# programmer-shield.net
KiCad netlist of a schematic drawn in EAGLE
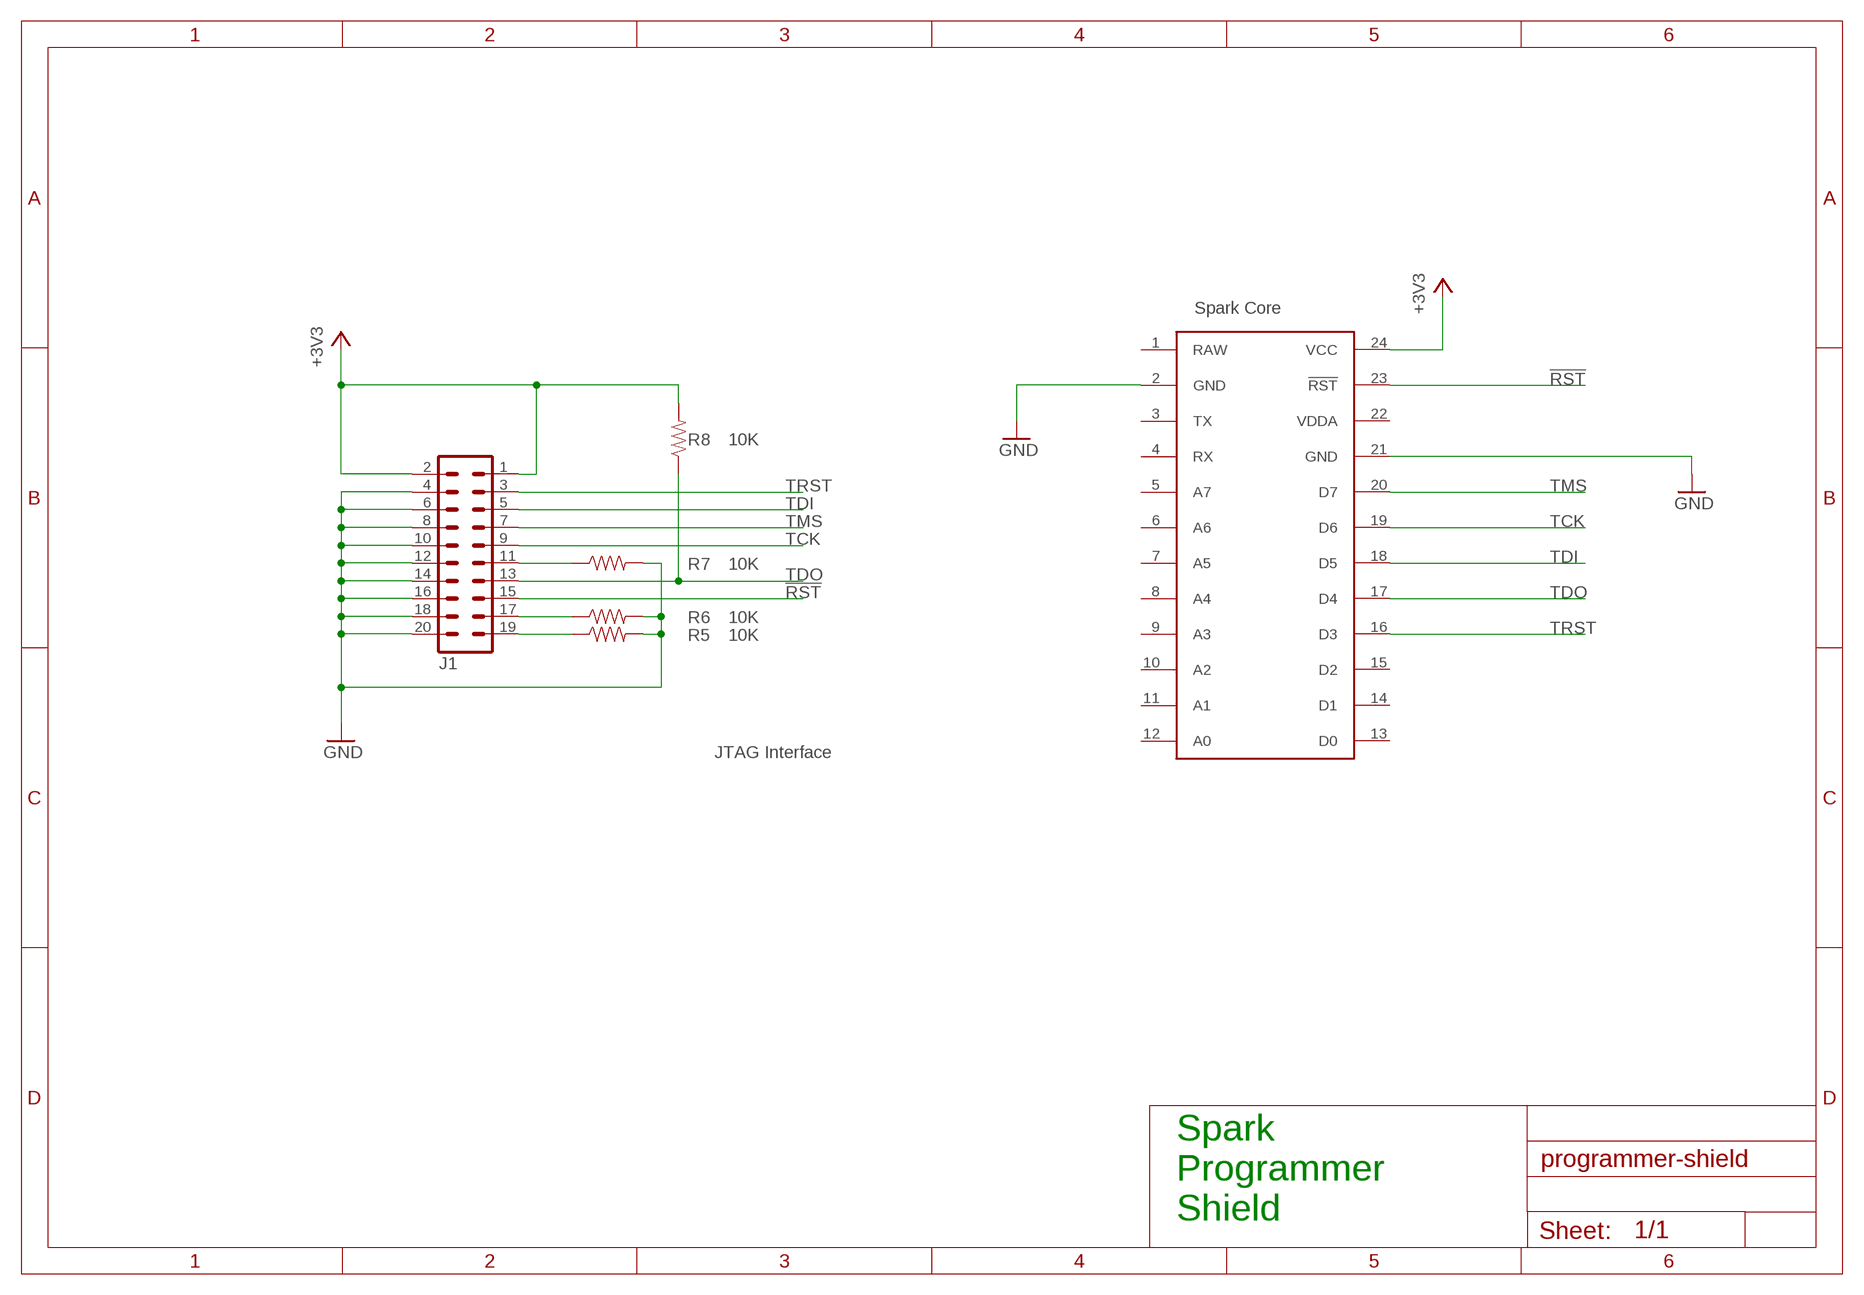
[diagram p0: schematic, sheet 1]

(export (version "E")
  (design (tool "Eeschema 10.0.6"))
  (components
    (comp (ref "J1")
      (value "ML20")
      (footprint "eagle-import:ML20")
      (libsource (lib "eagle-import") (part "ML20"))
    )
    (comp (ref "R5")
      (value "10K")
      (footprint "eagle-import:AXIAL-0.3")
      (libsource (lib "eagle-import") (part "RESISTORAXIAL-0.3"))
    )
    (comp (ref "R6")
      (value "10K")
      (footprint "eagle-import:AXIAL-0.3")
      (libsource (lib "eagle-import") (part "RESISTORAXIAL-0.3"))
    )
    (comp (ref "R7")
      (value "10K")
      (footprint "eagle-import:AXIAL-0.3")
      (libsource (lib "eagle-import") (part "RESISTORAXIAL-0.3"))
    )
    (comp (ref "R8")
      (value "10K")
      (footprint "eagle-import:AXIAL-0.3")
      (libsource (lib "eagle-import") (part "RESISTORAXIAL-0.3"))
    )
    (comp (ref "U$1")
      (value "SPARK_CORECORE")
      (footprint "eagle-import:SPARK_CORE")
      (libsource (lib "eagle-import") (part "SPARK_CORECORE"))
    )
  )
  (nets
    (net (code "1") (name "+3V3") (class "Default")
      (node (ref "J1") (pin "1") (pinfunction "1_1") (pintype "passive"))
      (node (ref "J1") (pin "2") (pinfunction "2_2") (pintype "passive"))
      (node (ref "R8") (pin "P$2") (pinfunction "2_P$2") (pintype "passive"))
      (node (ref "U$1") (pin "24") (pinfunction "VCC_24") (pintype "power_in"))
    )
    (net (code "2") (name "/RAW") (class "Default")
      (node (ref "U$1") (pin "1") (pinfunction "RAW_1") (pintype "power_in"))
    )
    (net (code "3") (name "/TCK") (class "Default")
      (node (ref "J1") (pin "9") (pinfunction "9_9") (pintype "passive"))
      (node (ref "U$1") (pin "19") (pinfunction "D6_19") (pintype "bidirectional"))
    )
    (net (code "4") (name "/TDI") (class "Default")
      (node (ref "J1") (pin "5") (pinfunction "5_5") (pintype "passive"))
      (node (ref "U$1") (pin "18") (pinfunction "D5_18") (pintype "bidirectional"))
    )
    (net (code "5") (name "/TDO") (class "Default")
      (node (ref "J1") (pin "13") (pinfunction "13_13") (pintype "passive"))
      (node (ref "R8") (pin "P$1") (pinfunction "1_P$1") (pintype "passive"))
      (node (ref "U$1") (pin "17") (pinfunction "D4_17") (pintype "bidirectional"))
    )
    (net (code "6") (name "/TMS") (class "Default")
      (node (ref "J1") (pin "7") (pinfunction "7_7") (pintype "passive"))
      (node (ref "U$1") (pin "20") (pinfunction "D7_20") (pintype "bidirectional"))
    )
    (net (code "7") (name "/TRST") (class "Default")
      (node (ref "J1") (pin "3") (pinfunction "3_3") (pintype "passive"))
      (node (ref "U$1") (pin "16") (pinfunction "D3_16") (pintype "bidirectional"))
    )
    (net (code "8") (name "/VDDA") (class "Default")
      (node (ref "U$1") (pin "22") (pinfunction "VDDA_22") (pintype "power_in"))
    )
    (net (code "9") (name "/~{RST}") (class "Default")
      (node (ref "J1") (pin "15") (pinfunction "15_15") (pintype "passive"))
      (node (ref "U$1") (pin "23") (pinfunction "~{RST}_23") (pintype "bidirectional"))
    )
    (net (code "10") (name "GND") (class "Default")
      (node (ref "J1") (pin "10") (pinfunction "10_10") (pintype "passive"))
      (node (ref "J1") (pin "12") (pinfunction "12_12") (pintype "passive"))
      (node (ref "J1") (pin "14") (pinfunction "14_14") (pintype "passive"))
      (node (ref "J1") (pin "16") (pinfunction "16_16") (pintype "passive"))
      (node (ref "J1") (pin "18") (pinfunction "18_18") (pintype "passive"))
      (node (ref "J1") (pin "20") (pinfunction "20_20") (pintype "passive"))
      (node (ref "J1") (pin "4") (pinfunction "4_4") (pintype "passive"))
      (node (ref "J1") (pin "6") (pinfunction "6_6") (pintype "passive"))
      (node (ref "J1") (pin "8") (pinfunction "8_8") (pintype "passive"))
      (node (ref "R5") (pin "P$2") (pinfunction "2_P$2") (pintype "passive"))
      (node (ref "R6") (pin "P$2") (pinfunction "2_P$2") (pintype "passive"))
      (node (ref "R7") (pin "P$2") (pinfunction "2_P$2") (pintype "passive"))
      (node (ref "U$1") (pin "2") (pinfunction "GND_2") (pintype "power_in"))
      (node (ref "U$1") (pin "21") (pinfunction "GND_21") (pintype "power_in"))
    )
    (net (code "11") (name "Net-(R5-1)") (class "Default")
      (node (ref "J1") (pin "19") (pinfunction "19_19") (pintype "passive"))
      (node (ref "R5") (pin "P$1") (pinfunction "1_P$1") (pintype "passive"))
    )
    (net (code "12") (name "Net-(R6-1)") (class "Default")
      (node (ref "J1") (pin "17") (pinfunction "17_17") (pintype "passive"))
      (node (ref "R6") (pin "P$1") (pinfunction "1_P$1") (pintype "passive"))
    )
    (net (code "13") (name "Net-(R7-1)") (class "Default")
      (node (ref "J1") (pin "11") (pinfunction "11_11") (pintype "passive"))
      (node (ref "R7") (pin "P$1") (pinfunction "1_P$1") (pintype "passive"))
    )
    (net (code "14") (name "unconnected-(U$1-A0-Pad12)") (class "Default")
      (node (ref "U$1") (pin "12") (pinfunction "A0_12") (pintype "bidirectional"))
    )
    (net (code "15") (name "unconnected-(U$1-A1-Pad11)") (class "Default")
      (node (ref "U$1") (pin "11") (pinfunction "A1_11") (pintype "bidirectional"))
    )
    (net (code "16") (name "unconnected-(U$1-A2-Pad10)") (class "Default")
      (node (ref "U$1") (pin "10") (pinfunction "A2_10") (pintype "bidirectional"))
    )
    (net (code "17") (name "unconnected-(U$1-A3-Pad9)") (class "Default")
      (node (ref "U$1") (pin "9") (pinfunction "A3_9") (pintype "bidirectional"))
    )
    (net (code "18") (name "unconnected-(U$1-A4-Pad8)") (class "Default")
      (node (ref "U$1") (pin "8") (pinfunction "A4_8") (pintype "bidirectional"))
    )
    (net (code "19") (name "unconnected-(U$1-A5-Pad7)") (class "Default")
      (node (ref "U$1") (pin "7") (pinfunction "A5_7") (pintype "bidirectional"))
    )
    (net (code "20") (name "unconnected-(U$1-A6-Pad6)") (class "Default")
      (node (ref "U$1") (pin "6") (pinfunction "A6_6") (pintype "bidirectional"))
    )
    (net (code "21") (name "unconnected-(U$1-A7-Pad5)") (class "Default")
      (node (ref "U$1") (pin "5") (pinfunction "A7_5") (pintype "bidirectional"))
    )
    (net (code "22") (name "unconnected-(U$1-D0-Pad13)") (class "Default")
      (node (ref "U$1") (pin "13") (pinfunction "D0_13") (pintype "bidirectional"))
    )
    (net (code "23") (name "unconnected-(U$1-D1-Pad14)") (class "Default")
      (node (ref "U$1") (pin "14") (pinfunction "D1_14") (pintype "bidirectional"))
    )
    (net (code "24") (name "unconnected-(U$1-D2-Pad15)") (class "Default")
      (node (ref "U$1") (pin "15") (pinfunction "D2_15") (pintype "bidirectional"))
    )
    (net (code "25") (name "unconnected-(U$1-RX-Pad4)") (class "Default")
      (node (ref "U$1") (pin "4") (pinfunction "RX_4") (pintype "bidirectional"))
    )
    (net (code "26") (name "unconnected-(U$1-TX-Pad3)") (class "Default")
      (node (ref "U$1") (pin "3") (pinfunction "TX_3") (pintype "bidirectional"))
    )
  )
)
